# arBot-v2.net
KiCad netlist of a schematic drawn in EAGLE
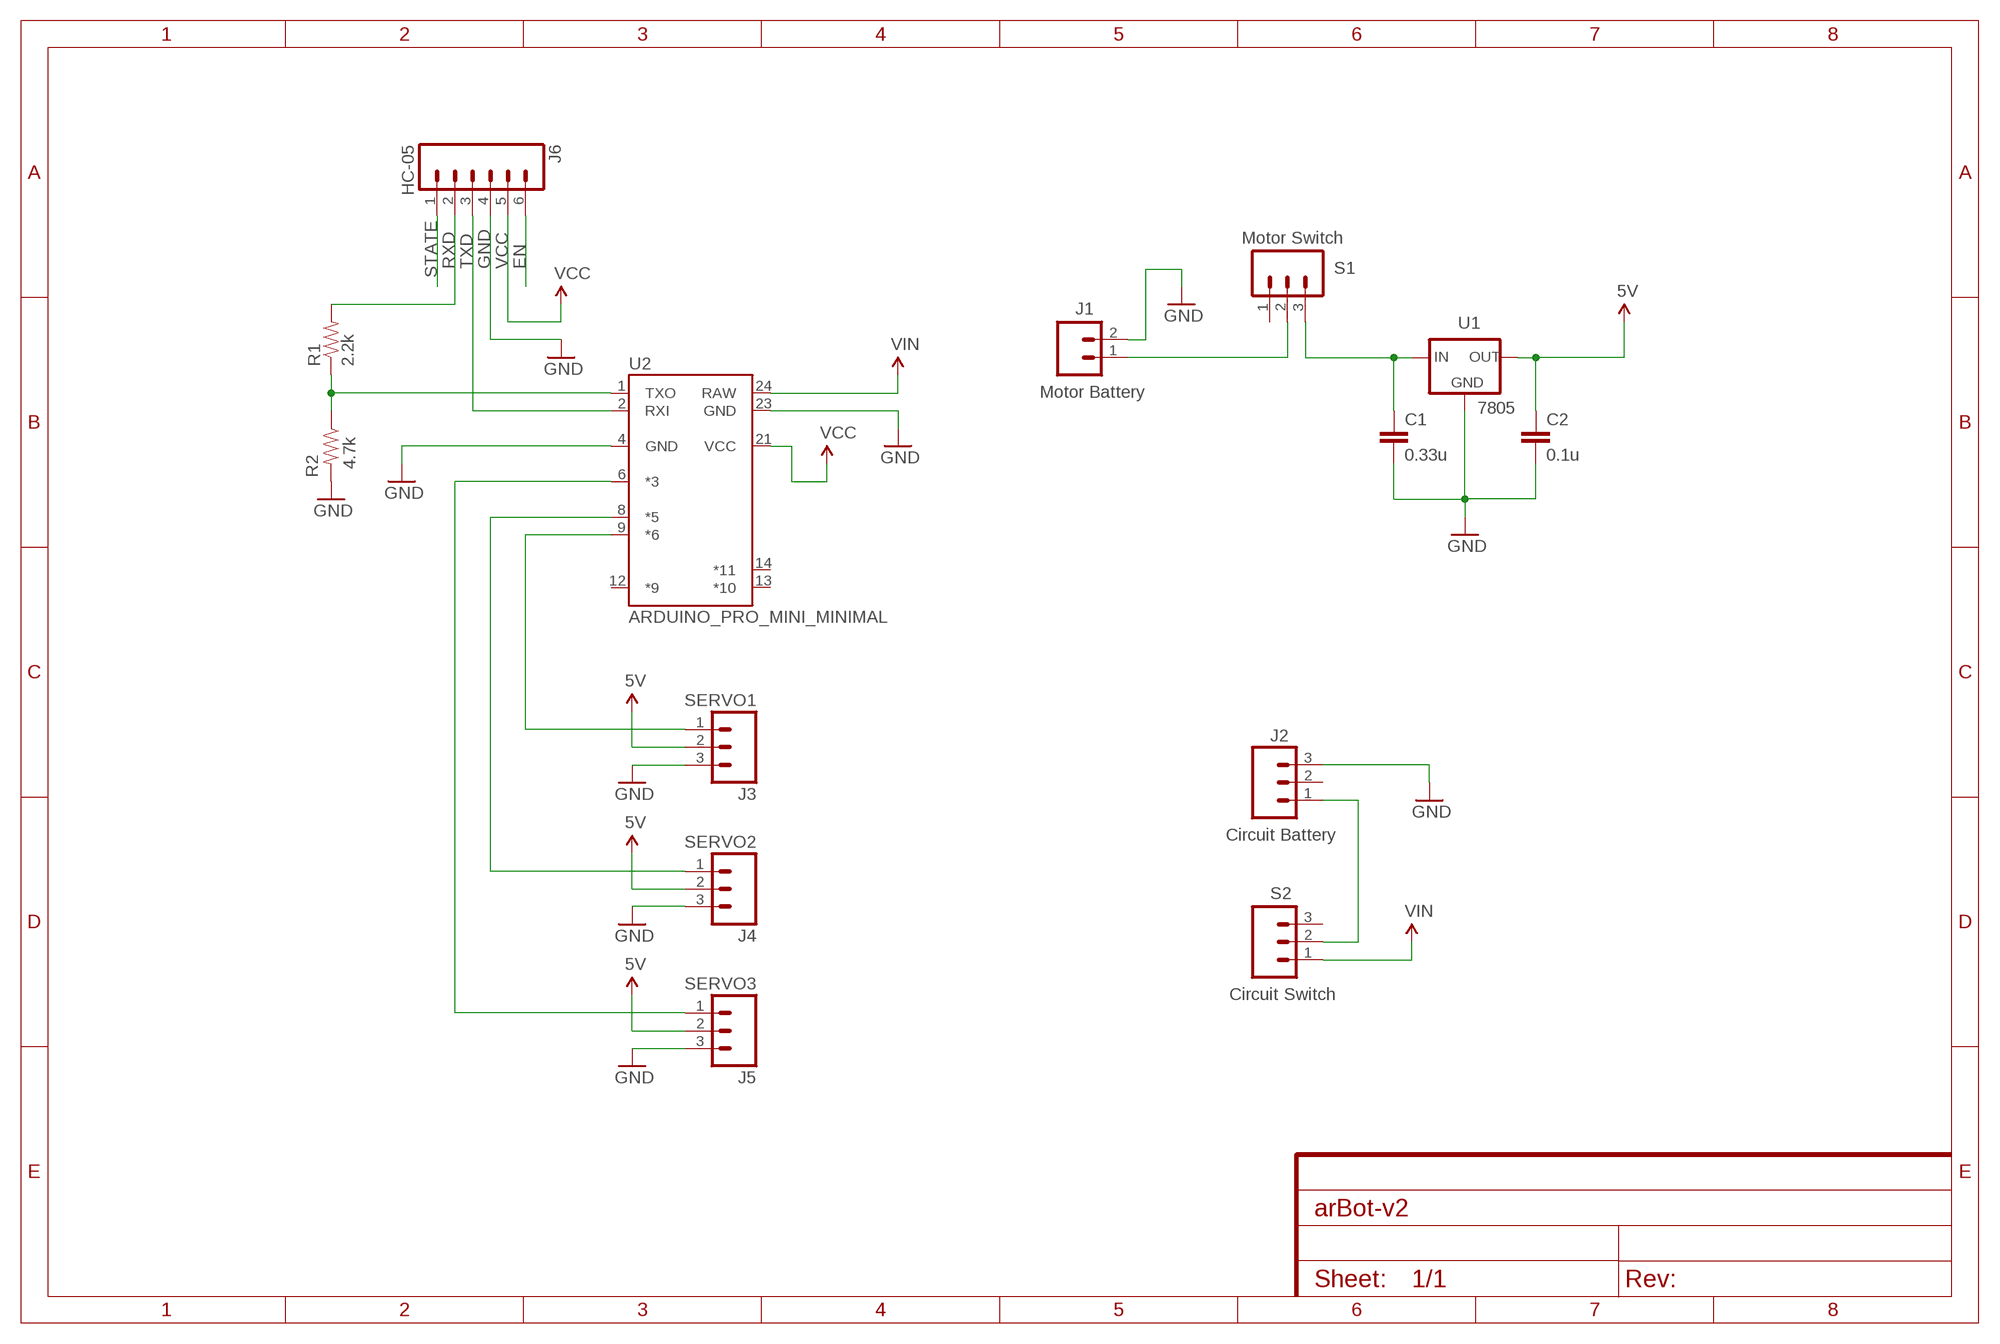
[diagram p0: schematic, sheet 1]

(export (version "E")
  (design (tool "Eeschema 10.0.6"))
  (components
    (comp (ref "C1")
      (value "0.33u")
      (footprint "eagle-import:CAP-PTH-SMALL")
      (libsource (lib "eagle-import") (part "CAPPTH"))
    )
    (comp (ref "C2")
      (value "0.1u")
      (footprint "eagle-import:CAP-PTH-SMALL")
      (libsource (lib "eagle-import") (part "CAPPTH"))
    )
    (comp (ref "J1")
      (value "Motor Battery")
      (footprint "eagle-import:SCREWTERMINAL-5MM-2")
      (libsource (lib "eagle-import") (part "M025MM"))
    )
    (comp (ref "J2")
      (value "Circuit Battery")
      (footprint "eagle-import:1X03_LONGPADS")
      (libsource (lib "eagle-import") (part "M03LONGPADS"))
    )
    (comp (ref "J3")
      (value "SERVO1")
      (footprint "eagle-import:1X03_LONGPADS")
      (libsource (lib "eagle-import") (part "M03LONGPADS"))
    )
    (comp (ref "J4")
      (value "SERVO2")
      (footprint "eagle-import:1X03_LONGPADS")
      (libsource (lib "eagle-import") (part "M03LONGPADS"))
    )
    (comp (ref "J5")
      (value "SERVO3")
      (footprint "eagle-import:1X03_LONGPADS")
      (libsource (lib "eagle-import") (part "M03LONGPADS"))
    )
    (comp (ref "J6")
      (value "HC-05")
      (footprint "eagle-import:1X06_LOCK_LONGPADS")
      (libsource (lib "eagle-import") (part "M06LOCK_LONGPADS"))
    )
    (comp (ref "R1")
      (value "2.2k")
      (footprint "eagle-import:AXIAL-0.3-KIT")
      (libsource (lib "eagle-import") (part "RESISTORKIT"))
    )
    (comp (ref "R2")
      (value "4.7k")
      (footprint "eagle-import:AXIAL-0.3-KIT")
      (libsource (lib "eagle-import") (part "RESISTORKIT"))
    )
    (comp (ref "S1")
      (value "Motor Switch")
      (footprint "eagle-import:SCREWTERMINAL-5MM-3")
      (libsource (lib "eagle-import") (part "M03-SCREW-5MM"))
    )
    (comp (ref "S2")
      (value "Circuit Switch")
      (footprint "eagle-import:1X03_LOCK_LONGPADS")
      (libsource (lib "eagle-import") (part "M03LOCK_LONGPADS"))
    )
    (comp (ref "U1")
      (value "7805")
      (footprint "eagle-import:TO-220-ALT")
      (libsource (lib "eagle-import") (part "V_REG_78XX-TO-220"))
    )
    (comp (ref "U2")
      (value "ARDUINO_PRO_MINI_MINIMAL")
      (footprint "eagle-import:ARDUINO_PRO_MINI_MINIMAL")
      (libsource (lib "eagle-import") (part "ARDUINO_PRO_MINI_MINIMAL"))
    )
  )
  (nets
    (net (code "1") (name "/EN") (class "Default")
      (node (ref "J6") (pin "6") (pinfunction "6_6") (pintype "passive"))
    )
    (net (code "2") (name "/RXD") (class "Default")
      (node (ref "J6") (pin "2") (pinfunction "2_2") (pintype "passive"))
      (node (ref "R1") (pin "P$2") (pinfunction "2_P$2") (pintype "passive"))
    )
    (net (code "3") (name "/STATE") (class "Default")
      (node (ref "J6") (pin "1") (pinfunction "1_1") (pintype "passive"))
    )
    (net (code "4") (name "/TXD") (class "Default")
      (node (ref "J6") (pin "3") (pinfunction "3_3") (pintype "passive"))
      (node (ref "U2") (pin "2") (pinfunction "RXI_2") (pintype "bidirectional"))
    )
    (net (code "5") (name "5V") (class "Default")
      (node (ref "C2") (pin "1") (pinfunction "1_1") (pintype "passive"))
      (node (ref "J3") (pin "2") (pinfunction "2_2") (pintype "passive"))
      (node (ref "J4") (pin "2") (pinfunction "2_2") (pintype "passive"))
      (node (ref "J5") (pin "2") (pinfunction "2_2") (pintype "passive"))
      (node (ref "U1") (pin "OUT") (pinfunction "OUT_OUT") (pintype "passive"))
    )
    (net (code "6") (name "GND") (class "Default")
      (node (ref "C1") (pin "2") (pinfunction "2_2") (pintype "passive"))
      (node (ref "C2") (pin "2") (pinfunction "2_2") (pintype "passive"))
      (node (ref "J1") (pin "2") (pinfunction "2_2") (pintype "passive"))
      (node (ref "J2") (pin "3") (pinfunction "3_3") (pintype "passive"))
      (node (ref "J3") (pin "3") (pinfunction "3_3") (pintype "passive"))
      (node (ref "J4") (pin "3") (pinfunction "3_3") (pintype "passive"))
      (node (ref "J5") (pin "3") (pinfunction "3_3") (pintype "passive"))
      (node (ref "J6") (pin "4") (pinfunction "4_4") (pintype "passive"))
      (node (ref "R2") (pin "P$2") (pinfunction "2_P$2") (pintype "passive"))
      (node (ref "U1") (pin "GND") (pinfunction "GND_GND") (pintype "input"))
      (node (ref "U2") (pin "23") (pinfunction "GND_23") (pintype "bidirectional"))
      (node (ref "U2") (pin "4") (pinfunction "GND_4") (pintype "bidirectional"))
    )
    (net (code "7") (name "Net-(C1-Pad1)") (class "Default")
      (node (ref "C1") (pin "1") (pinfunction "1_1") (pintype "passive"))
      (node (ref "S1") (pin "3") (pinfunction "3_3") (pintype "passive"))
      (node (ref "U1") (pin "IN") (pinfunction "IN_IN") (pintype "input"))
    )
    (net (code "8") (name "Net-(J1-Pad1)") (class "Default")
      (node (ref "J1") (pin "1") (pinfunction "1_1") (pintype "passive"))
      (node (ref "S1") (pin "2") (pinfunction "2_2") (pintype "passive"))
    )
    (net (code "9") (name "Net-(J2-Pad1)") (class "Default")
      (node (ref "J2") (pin "1") (pinfunction "1_1") (pintype "passive"))
      (node (ref "S2") (pin "2") (pinfunction "2_2") (pintype "passive"))
    )
    (net (code "10") (name "Net-(R1-1)") (class "Default")
      (node (ref "R1") (pin "P$1") (pinfunction "1_P$1") (pintype "passive"))
      (node (ref "R2") (pin "P$1") (pinfunction "1_P$1") (pintype "passive"))
      (node (ref "U2") (pin "1") (pinfunction "TXO_1") (pintype "bidirectional"))
    )
    (net (code "11") (name "Net-(U2-*3)") (class "Default")
      (node (ref "J5") (pin "1") (pinfunction "1_1") (pintype "passive"))
      (node (ref "U2") (pin "6") (pinfunction "*3_6") (pintype "bidirectional"))
    )
    (net (code "12") (name "Net-(U2-*5)") (class "Default")
      (node (ref "J4") (pin "1") (pinfunction "1_1") (pintype "passive"))
      (node (ref "U2") (pin "8") (pinfunction "*5_8") (pintype "bidirectional"))
    )
    (net (code "13") (name "Net-(U2-*6)") (class "Default")
      (node (ref "J3") (pin "1") (pinfunction "1_1") (pintype "passive"))
      (node (ref "U2") (pin "9") (pinfunction "*6_9") (pintype "bidirectional"))
    )
    (net (code "14") (name "VCC") (class "Default")
      (node (ref "J6") (pin "5") (pinfunction "5_5") (pintype "passive"))
      (node (ref "U2") (pin "21") (pinfunction "VCC_21") (pintype "bidirectional"))
    )
    (net (code "15") (name "VIN") (class "Default")
      (node (ref "S2") (pin "1") (pinfunction "1_1") (pintype "passive"))
      (node (ref "U2") (pin "24") (pinfunction "RAW_24") (pintype "bidirectional"))
    )
    (net (code "16") (name "unconnected-(J2-Pad2)") (class "Default")
      (node (ref "J2") (pin "2") (pinfunction "2_2") (pintype "passive"))
    )
    (net (code "17") (name "unconnected-(S1-Pad1)") (class "Default")
      (node (ref "S1") (pin "1") (pinfunction "1_1") (pintype "passive"))
    )
    (net (code "18") (name "unconnected-(S2-Pad3)") (class "Default")
      (node (ref "S2") (pin "3") (pinfunction "3_3") (pintype "passive"))
    )
    (net (code "19") (name "unconnected-(U2-*9-Pad12)") (class "Default")
      (node (ref "U2") (pin "12") (pinfunction "*9_12") (pintype "bidirectional"))
    )
    (net (code "20") (name "unconnected-(U2-*10-Pad13)") (class "Default")
      (node (ref "U2") (pin "13") (pinfunction "*10_13") (pintype "bidirectional"))
    )
    (net (code "21") (name "unconnected-(U2-*11-Pad14)") (class "Default")
      (node (ref "U2") (pin "14") (pinfunction "*11_14") (pintype "bidirectional"))
    )
  )
)
